# max30105-breakout.net
KiCad netlist of a schematic drawn in EAGLE
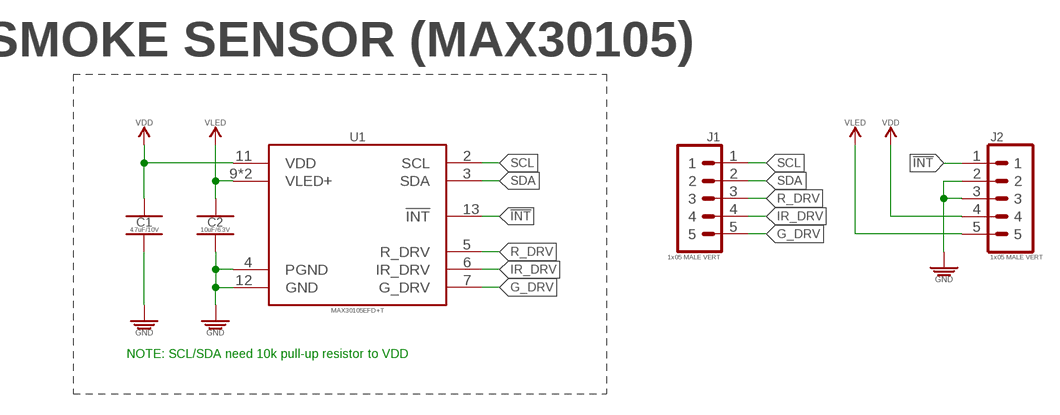
[diagram p0: schematic, sheet 1]

(export (version "E")
  (design (tool "Eeschema 10.0.6"))
  (components
    (comp (ref "C1")
      (value "4.7uF/10V")
      (footprint "eagle-import:CAPC1005X55_SMD-0402")
      (fields (field (name "MFR") "Samsung Electro-Mechanics") (field (name "MPN") "CL05A475MP5NRNC"))
      (libsource (lib "eagle-import") (part "4.7UF_CER_SMD-0402_10V-20%"))
    )
    (comp (ref "C2")
      (value "10uF/6.3V")
      (footprint "eagle-import:CAPC1005X55_SMD-0402")
      (fields
        (field (name "MFR") "Murata Electronics North America")
        (field (name "MPN") "GRM155C80J106ME11D")
      )
      (libsource (lib "eagle-import") (part "10UF_CER_SMD-0402_6.3V-20%"))
    )
    (comp (ref "J1")
      (value "1x05 MALE VERT")
      (footprint "eagle-import:HDRV5W64P254_1X5_1270X254X838B")
      (fields (field (name "MFR") "Sullins Connector Solutions") (field (name "MPN") "PEC05SAAN"))
      (libsource (lib "eagle-import") (part "1X05_PTH_VERT_MALE_2.54MM"))
    )
    (comp (ref "J2")
      (value "1x05 MALE VERT")
      (footprint "eagle-import:HDRV5W64P254_1X5_1270X254X838B")
      (fields (field (name "MFR") "Sullins Connector Solutions") (field (name "MPN") "PEC05SAAN"))
      (libsource (lib "eagle-import") (part "1X05_PTH_VERT_MALE_2.54MM"))
    )
    (comp (ref "U1")
      (value "MAX30105EFD+T")
      (footprint "eagle-import:SON80P330X560X165-14N")
      (fields (field (name "MFR") "Maxim Integrated"))
      (libsource (lib "eagle-import") (part "MAX30105EFD+T"))
    )
  )
  (nets
    (net (code "1") (name "/~{INT}") (class "Default")
      (node (ref "J2") (pin "1") (pinfunction "1_1") (pintype "passive"))
      (node (ref "U1") (pin "13") (pinfunction "~{INT}_13") (pintype "bidirectional"))
    )
    (net (code "2") (name "GND") (class "Default")
      (node (ref "C1") (pin "2") (pinfunction "2_2") (pintype "passive"))
      (node (ref "C2") (pin "2") (pinfunction "2_2") (pintype "passive"))
      (node (ref "J2") (pin "2") (pinfunction "2_2") (pintype "passive"))
      (node (ref "J2") (pin "3") (pinfunction "3_3") (pintype "passive"))
      (node (ref "U1") (pin "12") (pinfunction "GND_12") (pintype "power_in"))
      (node (ref "U1") (pin "4") (pinfunction "PGND_4") (pintype "power_in"))
    )
    (net (code "3") (name "G_DRV") (class "Default")
      (node (ref "J1") (pin "5") (pinfunction "5_5") (pintype "passive"))
      (node (ref "U1") (pin "7") (pinfunction "G_DRV_7") (pintype "bidirectional"))
    )
    (net (code "4") (name "IR_DRV") (class "Default")
      (node (ref "J1") (pin "4") (pinfunction "4_4") (pintype "passive"))
      (node (ref "U1") (pin "6") (pinfunction "IR_DRV_6") (pintype "bidirectional"))
    )
    (net (code "5") (name "R_DRV") (class "Default")
      (node (ref "J1") (pin "3") (pinfunction "3_3") (pintype "passive"))
      (node (ref "U1") (pin "5") (pinfunction "R_DRV_5") (pintype "bidirectional"))
    )
    (net (code "6") (name "SCL") (class "Default")
      (node (ref "J1") (pin "1") (pinfunction "1_1") (pintype "passive"))
      (node (ref "U1") (pin "2") (pinfunction "SCL_2") (pintype "bidirectional"))
    )
    (net (code "7") (name "SDA") (class "Default")
      (node (ref "J1") (pin "2") (pinfunction "2_2") (pintype "passive"))
      (node (ref "U1") (pin "3") (pinfunction "SDA_3") (pintype "bidirectional"))
    )
    (net (code "8") (name "VDD") (class "Default")
      (node (ref "C1") (pin "1") (pinfunction "1_1") (pintype "passive"))
      (node (ref "J2") (pin "4") (pinfunction "4_4") (pintype "passive"))
      (node (ref "U1") (pin "11") (pinfunction "VDD_11") (pintype "power_in"))
    )
    (net (code "9") (name "VLED") (class "Default")
      (node (ref "C2") (pin "1") (pinfunction "1_1") (pintype "passive"))
      (node (ref "J2") (pin "5") (pinfunction "5_5") (pintype "passive"))
      (node (ref "U1") (pin "10") (pinfunction "VLED+_10") (pintype "power_in"))
      (node (ref "U1") (pin "9") (pinfunction "VLED+_9") (pintype "power_in"))
    )
  )
)
